# design.net
KiCad netlist of a schematic drawn in Altium Designer
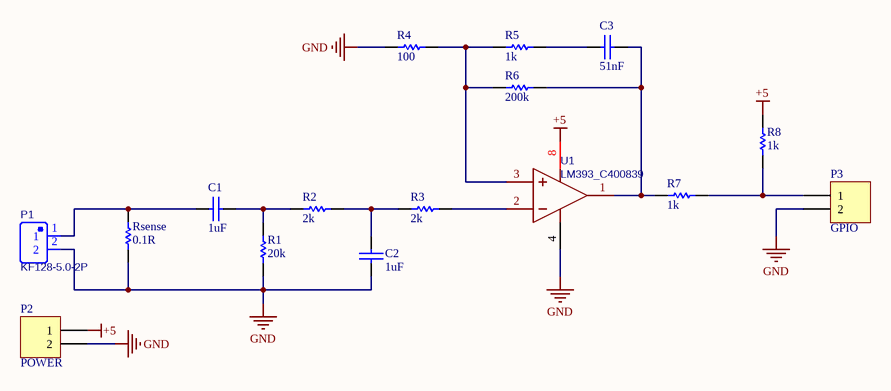
[diagram p0: 电流脉冲检测.SchDoc]

(export (version "E")
  (design (tool "Eeschema 10.0.6"))
  (components
    (comp (ref "C1")
      (value "1uF")
      (footprint "0805C")
      (description "Capacitor")
      (libsource (lib "SCHOFDylan") (part "CAP"))
    )
    (comp (ref "C2")
      (value "1uF")
      (footprint "0805C")
      (description "Capacitor")
      (libsource (lib "SCHOFDylan") (part "CAP"))
    )
    (comp (ref "C3") (value "51nF") (footprint "1206C") (libsource (lib "SCHOFDylan") (part "cap_1206")))
    (comp (ref "P1")
      (value "KF128-5.0-2P")
      (footprint "CONN-TH_P5.00_KF128-5.0-2P")
      (fields (field (name "BOM_SUPPLIER PART") "C474950") (field (name "CONTRIBUTOR") "LCSC"))
      (libsource (lib "SCHOFDylan") (part "KF128-2P"))
    )
    (comp (ref "P2")
      (value "POWER")
      (footprint "HDR1X2")
      (description "Header, 2-Pin")
      (fields (field (name "PUBLISHER") "Altium Limited"))
      (libsource (lib "") (part "Header 2_1"))
    )
    (comp (ref "P3")
      (value "GPIO")
      (footprint "HDR1X2")
      (description "Header, 2-Pin")
      (fields (field (name "PUBLISHER") "Altium Limited"))
      (libsource (lib "SCHOFDylan") (part "Header 2"))
    )
    (comp (ref "R1")
      (value "20k")
      (footprint "0805R")
      (description "Resistor")
      (libsource (lib "SCHOFDylan") (part "Res1"))
    )
    (comp (ref "R2")
      (value "2k")
      (footprint "0805R")
      (description "Resistor")
      (libsource (lib "SCHOFDylan") (part "Res1"))
    )
    (comp (ref "R3")
      (value "2k")
      (footprint "0805R")
      (description "Resistor")
      (libsource (lib "SCHOFDylan") (part "Res1"))
    )
    (comp (ref "R4")
      (value "100")
      (footprint "0805R")
      (description "Resistor")
      (libsource (lib "SCHOFDylan") (part "Res1"))
    )
    (comp (ref "R5")
      (value "1k")
      (footprint "0805R")
      (description "Resistor")
      (libsource (lib "SCHOFDylan") (part "Res1"))
    )
    (comp (ref "R6")
      (value "200k")
      (footprint "0805R")
      (description "Resistor")
      (libsource (lib "SCHOFDylan") (part "Res1"))
    )
    (comp (ref "R7")
      (value "1k")
      (footprint "0805R")
      (description "Resistor")
      (libsource (lib "SCHOFDylan") (part "Res1"))
    )
    (comp (ref "R8")
      (value "1k")
      (footprint "0805R")
      (description "Resistor")
      (libsource (lib "SCHOFDylan") (part "Res1"))
    )
    (comp (ref "Rsense") (value "0.1R") (footprint "R2512") (libsource (lib "SCHOFDylan") (part "Rsense")))
    (comp (ref "U1")
      (value "LM393_C400839")
      (footprint "SOP-8_L4.9-W3.9-P1.27-LS6.0-BL")
      (fields
        (field (name "BOM_SUPPLIER PART") "C400839")
        (field (name "BOM_MANUFACTURER PART") "LM393")
        (field (name "SUBPART_NO") "2")
      )
      (libsource (lib "SCHOFDylan") (part "LM393_A"))
    )
  )
  (nets
    (net (code "1") (name "+5") (class "Default")
      (node (ref "P2") (pin "1") (pinfunction "1_1") (pintype "passive"))
      (node (ref "R8") (pin "2") (pinfunction "2_2") (pintype "passive"))
      (node (ref "U1") (pin "8") (pinfunction "VCC_8") (pintype "passive"))
    )
    (net (code "2") (name "GND") (class "Default")
      (node (ref "C2") (pin "1") (pinfunction "1_1") (pintype "passive"))
      (node (ref "P1") (pin "2") (pinfunction "2_2") (pintype "passive"))
      (node (ref "P2") (pin "2") (pinfunction "2_2") (pintype "passive"))
      (node (ref "P3") (pin "2") (pinfunction "2_2") (pintype "passive"))
      (node (ref "R1") (pin "1") (pinfunction "1_1") (pintype "passive"))
      (node (ref "R4") (pin "1") (pinfunction "1_1") (pintype "passive"))
      (node (ref "Rsense") (pin "2") (pinfunction "2_2") (pintype "passive"))
      (node (ref "U1") (pin "4") (pinfunction "GND_4") (pintype "passive"))
    )
    (net (code "3") (name "Net-(C1-Pad1)") (class "Default")
      (node (ref "C1") (pin "1") (pinfunction "1_1") (pintype "passive"))
      (node (ref "P1") (pin "1") (pinfunction "1_1") (pintype "passive"))
      (node (ref "Rsense") (pin "1") (pinfunction "1_1") (pintype "passive"))
    )
    (net (code "4") (name "Net-(C1-Pad2)") (class "Default")
      (node (ref "C1") (pin "2") (pinfunction "2_2") (pintype "passive"))
      (node (ref "R1") (pin "2") (pinfunction "2_2") (pintype "passive"))
      (node (ref "R2") (pin "1") (pinfunction "1_1") (pintype "passive"))
    )
    (net (code "5") (name "Net-(C2-Pad2)") (class "Default")
      (node (ref "C2") (pin "2") (pinfunction "2_2") (pintype "passive"))
      (node (ref "R2") (pin "2") (pinfunction "2_2") (pintype "passive"))
      (node (ref "R3") (pin "1") (pinfunction "1_1") (pintype "passive"))
    )
    (net (code "6") (name "Net-(C3-Pad1)") (class "Default")
      (node (ref "C3") (pin "1") (pinfunction "1_1") (pintype "passive"))
      (node (ref "R5") (pin "2") (pinfunction "2_2") (pintype "passive"))
    )
    (net (code "7") (name "Net-(P3-Pad1)") (class "Default")
      (node (ref "P3") (pin "1") (pinfunction "1_1") (pintype "passive"))
      (node (ref "R7") (pin "2") (pinfunction "2_2") (pintype "passive"))
      (node (ref "R8") (pin "1") (pinfunction "1_1") (pintype "passive"))
    )
    (net (code "8") (name "Net-(U1-INA+)") (class "Default")
      (node (ref "R4") (pin "2") (pinfunction "2_2") (pintype "passive"))
      (node (ref "R5") (pin "1") (pinfunction "1_1") (pintype "passive"))
      (node (ref "R6") (pin "1") (pinfunction "1_1") (pintype "passive"))
      (node (ref "U1") (pin "3") (pinfunction "INA+_3") (pintype "passive"))
    )
    (net (code "9") (name "Net-(U1-INA-)") (class "Default")
      (node (ref "R3") (pin "2") (pinfunction "2_2") (pintype "passive"))
      (node (ref "U1") (pin "2") (pinfunction "INA-_2") (pintype "passive"))
    )
    (net (code "10") (name "Net-(U1-OUTA)") (class "Default")
      (node (ref "C3") (pin "2") (pinfunction "2_2") (pintype "passive"))
      (node (ref "R6") (pin "2") (pinfunction "2_2") (pintype "passive"))
      (node (ref "R7") (pin "1") (pinfunction "1_1") (pintype "passive"))
      (node (ref "U1") (pin "1") (pinfunction "OUTA_1") (pintype "passive"))
    )
  )
)
